# GrblMainboard_-_v3_0.net
KiCad netlist of a schematic drawn in EAGLE
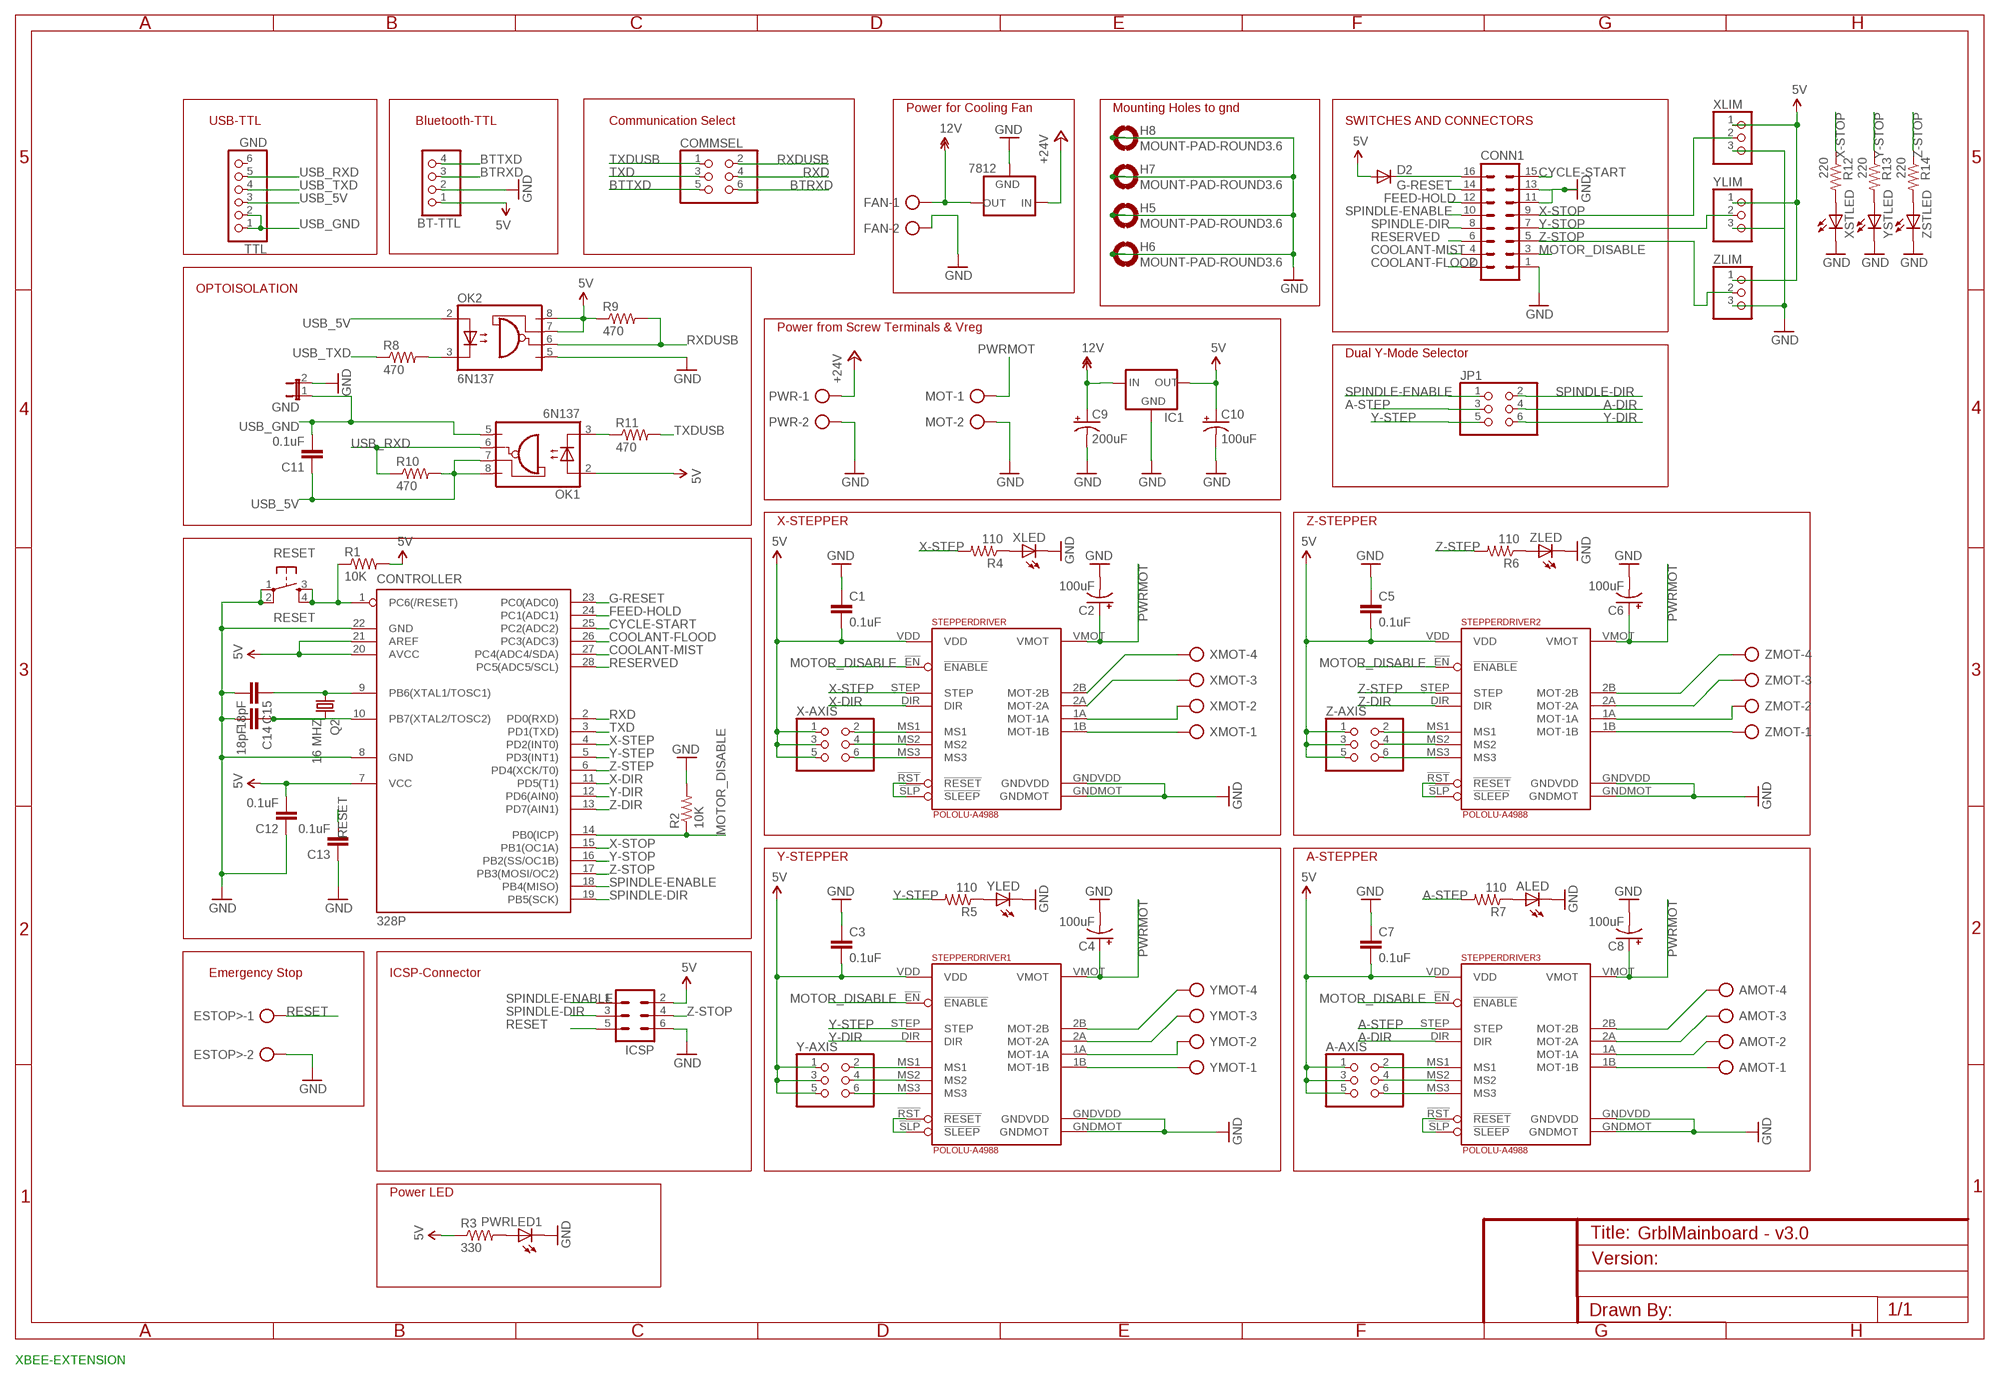
[diagram p0: schematic, sheet 1]

(export (version "E")
  (design (tool "Eeschema 10.0.6"))
  (components
    (comp (ref "328P")
      (value "CONTROLLER")
      (footprint "eagle-import:DIL28-3")
      (libsource (lib "eagle-import") (part "MEGA8-P"))
    )
    (comp (ref "7812")
      (value "V_REG_78XXSINK")
      (footprint "eagle-import:TO220-IGO")
      (libsource (lib "eagle-import") (part "V_REG_78XXSINK"))
    )
    (comp (ref "A-AXIS")
      (value "PINHD-2X3")
      (footprint "eagle-import:2X03")
      (libsource (lib "eagle-import") (part "PINHD-2X3"))
    )
    (comp (ref "ALED")
      (value "LED3MM")
      (footprint "eagle-import:LED3MM")
      (libsource (lib "eagle-import") (part "LED3MM"))
    )
    (comp (ref "AMOT")
      (value "AK500/4")
      (footprint "eagle-import:AK500_4")
      (libsource (lib "eagle-import") (part "AK500/4"))
    )
    (comp (ref "BT-TTL")
      (value "PINHD-1X4")
      (footprint "eagle-import:1X04")
      (libsource (lib "eagle-import") (part "PINHD-1X4"))
    )
    (comp (ref "C1")
      (value "0.1uF")
      (footprint "eagle-import:C025-025X050")
      (libsource (lib "eagle-import") (part "C-EU025-025X050"))
    )
    (comp (ref "C2")
      (value "100uF")
      (footprint "eagle-import:E3,5-8")
      (libsource (lib "eagle-import") (part "CPOL-USE3.5-8"))
    )
    (comp (ref "C3")
      (value "0.1uF")
      (footprint "eagle-import:C025-025X050")
      (libsource (lib "eagle-import") (part "C-EU025-025X050"))
    )
    (comp (ref "C4")
      (value "100uF")
      (footprint "eagle-import:E3,5-8")
      (libsource (lib "eagle-import") (part "CPOL-USE3.5-8"))
    )
    (comp (ref "C5")
      (value "0.1uF")
      (footprint "eagle-import:C025-025X050")
      (libsource (lib "eagle-import") (part "C-EU025-025X050"))
    )
    (comp (ref "C6")
      (value "100uF")
      (footprint "eagle-import:E3,5-8")
      (libsource (lib "eagle-import") (part "CPOL-USE3.5-8"))
    )
    (comp (ref "C7")
      (value "0.1uF")
      (footprint "eagle-import:C025-025X050")
      (libsource (lib "eagle-import") (part "C-EU025-025X050"))
    )
    (comp (ref "C8")
      (value "100uF")
      (footprint "eagle-import:E3,5-8")
      (libsource (lib "eagle-import") (part "CPOL-USE3.5-8"))
    )
    (comp (ref "C9")
      (value "200uF")
      (footprint "eagle-import:E2,5-6")
      (libsource (lib "eagle-import") (part "CPOL-USE2.5-6"))
    )
    (comp (ref "C10")
      (value "100uF")
      (footprint "eagle-import:E2,5-6")
      (libsource (lib "eagle-import") (part "CPOL-USE2.5-6"))
    )
    (comp (ref "C11")
      (value "0.1uF")
      (footprint "eagle-import:C025-025X050")
      (libsource (lib "eagle-import") (part "C-EU025-025X050"))
    )
    (comp (ref "C12")
      (value "0.1uF")
      (footprint "eagle-import:C025-025X050")
      (libsource (lib "eagle-import") (part "C-EU025-025X050"))
    )
    (comp (ref "C13")
      (value "0.1uF")
      (footprint "eagle-import:C025-025X050")
      (libsource (lib "eagle-import") (part "C-EU025-025X050"))
    )
    (comp (ref "C14")
      (value "18pF")
      (footprint "eagle-import:C025-025X050")
      (libsource (lib "eagle-import") (part "C-EU025-025X050"))
    )
    (comp (ref "C15")
      (value "18pF")
      (footprint "eagle-import:C025-025X050")
      (libsource (lib "eagle-import") (part "C-EU025-025X050"))
    )
    (comp (ref "COMMSEL")
      (value "PINHD-2X3")
      (footprint "eagle-import:2X03")
      (libsource (lib "eagle-import") (part "PINHD-2X3"))
    )
    (comp (ref "CONN1")
      (value "ML16")
      (footprint "eagle-import:ML16")
      (libsource (lib "eagle-import") (part "ML16"))
    )
    (comp (ref "D2")
      (value "DIODEPTH")
      (footprint "eagle-import:DIODE-1N4001")
      (libsource (lib "eagle-import") (part "DIODEPTH"))
    )
    (comp (ref "ESTOP>")
      (value "AK500/2")
      (footprint "eagle-import:AK500_2")
      (libsource (lib "eagle-import") (part "AK500/2"))
    )
    (comp (ref "FAN")
      (value "AK500/2")
      (footprint "eagle-import:AK500_2")
      (libsource (lib "eagle-import") (part "AK500/2"))
    )
    (comp (ref "GND")
      (value "JP1E")
      (footprint "eagle-import:JP1")
      (libsource (lib "eagle-import") (part "JP1E"))
    )
    (comp (ref "H5")
      (value "MOUNT-PAD-ROUND3.6")
      (footprint "eagle-import:3,6-PAD")
      (libsource (lib "eagle-import") (part "MOUNT-PAD-ROUND3.6"))
    )
    (comp (ref "H6")
      (value "MOUNT-PAD-ROUND3.6")
      (footprint "eagle-import:3,6-PAD")
      (libsource (lib "eagle-import") (part "MOUNT-PAD-ROUND3.6"))
    )
    (comp (ref "H7")
      (value "MOUNT-PAD-ROUND3.6")
      (footprint "eagle-import:3,6-PAD")
      (libsource (lib "eagle-import") (part "MOUNT-PAD-ROUND3.6"))
    )
    (comp (ref "H8")
      (value "MOUNT-PAD-ROUND3.6")
      (footprint "eagle-import:3,6-PAD")
      (libsource (lib "eagle-import") (part "MOUNT-PAD-ROUND3.6"))
    )
    (comp (ref "IC1")
      (value "V_REG_78XXSINK")
      (footprint "eagle-import:TO220-IGO")
      (libsource (lib "eagle-import") (part "V_REG_78XXSINK"))
    )
    (comp (ref "ICSP")
      (value "ML6")
      (footprint "eagle-import:ML6")
      (libsource (lib "eagle-import") (part "ML6"))
    )
    (comp (ref "JP1")
      (value "PINHD-2X3")
      (footprint "eagle-import:2X03")
      (libsource (lib "eagle-import") (part "PINHD-2X3"))
    )
    (comp (ref "MOT")
      (value "AK500/2")
      (footprint "eagle-import:AK500_2")
      (libsource (lib "eagle-import") (part "AK500/2"))
    )
    (comp (ref "OK1")
      (value "6N137")
      (footprint "eagle-import:DIL08")
      (libsource (lib "eagle-import") (part "6N137"))
    )
    (comp (ref "OK2")
      (value "6N137")
      (footprint "eagle-import:DIL08")
      (libsource (lib "eagle-import") (part "6N137"))
    )
    (comp (ref "PWR")
      (value "AK500/2")
      (footprint "eagle-import:AK500_2")
      (libsource (lib "eagle-import") (part "AK500/2"))
    )
    (comp (ref "PWRLED1")
      (value "LED3MM")
      (footprint "eagle-import:LED3MM")
      (libsource (lib "eagle-import") (part "LED3MM"))
    )
    (comp (ref "Q2")
      (value "16 MHZ")
      (footprint "eagle-import:HC49_S")
      (libsource (lib "eagle-import") (part "CRYSTALHC49S"))
    )
    (comp (ref "R1")
      (value "10K")
      (footprint "eagle-import:AXIAL-0.3")
      (libsource (lib "eagle-import") (part "RESISTORAXIAL-0.3"))
    )
    (comp (ref "R2")
      (value "10K")
      (footprint "eagle-import:AXIAL-0.3")
      (libsource (lib "eagle-import") (part "RESISTORAXIAL-0.3"))
    )
    (comp (ref "R3")
      (value "330")
      (footprint "eagle-import:1_6W-RES")
      (libsource (lib "eagle-import") (part "RESISTORPTH-1/6W"))
    )
    (comp (ref "R4")
      (value "110")
      (footprint "eagle-import:AXIAL-0.3")
      (libsource (lib "eagle-import") (part "RESISTORAXIAL-0.3"))
    )
    (comp (ref "R5")
      (value "110")
      (footprint "eagle-import:AXIAL-0.3")
      (libsource (lib "eagle-import") (part "RESISTORAXIAL-0.3"))
    )
    (comp (ref "R6")
      (value "110")
      (footprint "eagle-import:AXIAL-0.3")
      (libsource (lib "eagle-import") (part "RESISTORAXIAL-0.3"))
    )
    (comp (ref "R7")
      (value "110")
      (footprint "eagle-import:AXIAL-0.3")
      (libsource (lib "eagle-import") (part "RESISTORAXIAL-0.3"))
    )
    (comp (ref "R8")
      (value "470")
      (footprint "eagle-import:AXIAL-0.3")
      (libsource (lib "eagle-import") (part "RESISTORAXIAL-0.3"))
    )
    (comp (ref "R9")
      (value "470")
      (footprint "eagle-import:AXIAL-0.3")
      (libsource (lib "eagle-import") (part "RESISTORAXIAL-0.3"))
    )
    (comp (ref "R10")
      (value "470")
      (footprint "eagle-import:AXIAL-0.3")
      (libsource (lib "eagle-import") (part "RESISTORAXIAL-0.3"))
    )
    (comp (ref "R11")
      (value "470")
      (footprint "eagle-import:AXIAL-0.3")
      (libsource (lib "eagle-import") (part "RESISTORAXIAL-0.3"))
    )
    (comp (ref "R12")
      (value "220")
      (footprint "eagle-import:AXIAL-0.3")
      (libsource (lib "eagle-import") (part "RESISTORAXIAL-0.3"))
    )
    (comp (ref "R13")
      (value "220")
      (footprint "eagle-import:AXIAL-0.3")
      (libsource (lib "eagle-import") (part "RESISTORAXIAL-0.3"))
    )
    (comp (ref "R14")
      (value "220")
      (footprint "eagle-import:AXIAL-0.3")
      (libsource (lib "eagle-import") (part "RESISTORAXIAL-0.3"))
    )
    (comp (ref "RESET")
      (value "RESET")
      (footprint "eagle-import:TACTILE-PTH")
      (libsource (lib "eagle-import") (part "TAC_SWITCHPTH"))
    )
    (comp (ref "STEPPERDRIVER")
      (value "POLOLU-A4988")
      (footprint "eagle-import:POLOLU-ALLEGRO-PTH")
      (libsource (lib "eagle-import") (part "POLOLU-ALLEGRO"))
    )
    (comp (ref "STEPPERDRIVER1")
      (value "POLOLU-A4988")
      (footprint "eagle-import:POLOLU-ALLEGRO-PTH")
      (libsource (lib "eagle-import") (part "POLOLU-ALLEGRO"))
    )
    (comp (ref "STEPPERDRIVER2")
      (value "POLOLU-A4988")
      (footprint "eagle-import:POLOLU-ALLEGRO-PTH")
      (libsource (lib "eagle-import") (part "POLOLU-ALLEGRO"))
    )
    (comp (ref "STEPPERDRIVER3")
      (value "POLOLU-A4988")
      (footprint "eagle-import:POLOLU-ALLEGRO-PTH")
      (libsource (lib "eagle-import") (part "POLOLU-ALLEGRO"))
    )
    (comp (ref "TTL")
      (value "GND")
      (footprint "eagle-import:1X06")
      (libsource (lib "eagle-import") (part "PINHD-1X6"))
    )
    (comp (ref "X-AXIS")
      (value "PINHD-2X3")
      (footprint "eagle-import:2X03")
      (libsource (lib "eagle-import") (part "PINHD-2X3"))
    )
    (comp (ref "XLED")
      (value "LED3MM")
      (footprint "eagle-import:LED3MM")
      (libsource (lib "eagle-import") (part "LED3MM"))
    )
    (comp (ref "XLIM")
      (value "PINHD-1X3")
      (footprint "eagle-import:1X03")
      (libsource (lib "eagle-import") (part "PINHD-1X3"))
    )
    (comp (ref "XMOT")
      (value "AK500/4")
      (footprint "eagle-import:AK500_4")
      (libsource (lib "eagle-import") (part "AK500/4"))
    )
    (comp (ref "XSTLED")
      (value "LED3MM")
      (footprint "eagle-import:LED3MM")
      (libsource (lib "eagle-import") (part "LED3MM"))
    )
    (comp (ref "Y-AXIS")
      (value "PINHD-2X3")
      (footprint "eagle-import:2X03")
      (libsource (lib "eagle-import") (part "PINHD-2X3"))
    )
    (comp (ref "YLED")
      (value "LED3MM")
      (footprint "eagle-import:LED3MM")
      (libsource (lib "eagle-import") (part "LED3MM"))
    )
    (comp (ref "YLIM")
      (value "PINHD-1X3")
      (footprint "eagle-import:1X03")
      (libsource (lib "eagle-import") (part "PINHD-1X3"))
    )
    (comp (ref "YMOT")
      (value "AK500/4")
      (footprint "eagle-import:AK500_4")
      (libsource (lib "eagle-import") (part "AK500/4"))
    )
    (comp (ref "YSTLED")
      (value "LED3MM")
      (footprint "eagle-import:LED3MM")
      (libsource (lib "eagle-import") (part "LED3MM"))
    )
    (comp (ref "Z-AXIS")
      (value "PINHD-2X3")
      (footprint "eagle-import:2X03")
      (libsource (lib "eagle-import") (part "PINHD-2X3"))
    )
    (comp (ref "ZLED")
      (value "LED3MM")
      (footprint "eagle-import:LED3MM")
      (libsource (lib "eagle-import") (part "LED3MM"))
    )
    (comp (ref "ZLIM")
      (value "PINHD-1X3")
      (footprint "eagle-import:1X03")
      (libsource (lib "eagle-import") (part "PINHD-1X3"))
    )
    (comp (ref "ZMOT")
      (value "AK500/4")
      (footprint "eagle-import:AK500_4")
      (libsource (lib "eagle-import") (part "AK500/4"))
    )
    (comp (ref "ZSTLED")
      (value "LED3MM")
      (footprint "eagle-import:LED3MM")
      (libsource (lib "eagle-import") (part "LED3MM"))
    )
  )
  (nets
    (net (code "1") (name "+24V") (class "Default")
      (node (ref "7812") (pin "IN") (pinfunction "IN_IN") (pintype "input"))
      (node (ref "PWR") (pin "1") (pinfunction "KL_1") (pintype "passive"))
    )
    (net (code "2") (name "/A-DIR") (class "Default")
      (node (ref "JP1") (pin "4") (pinfunction "4_4") (pintype "passive"))
      (node (ref "STEPPERDRIVER3") (pin "DIR") (pinfunction "DIR_DIR") (pintype "bidirectional"))
    )
    (net (code "3") (name "/A-STEP") (class "Default")
      (node (ref "JP1") (pin "3") (pinfunction "3_3") (pintype "passive"))
      (node (ref "R7") (pin "P$2") (pinfunction "2_P$2") (pintype "passive"))
      (node (ref "STEPPERDRIVER3") (pin "STEP") (pinfunction "STEP_STEP") (pintype "bidirectional"))
    )
    (net (code "4") (name "/BTRXD") (class "Default")
      (node (ref "BT-TTL") (pin "3") (pinfunction "3_3") (pintype "passive"))
      (node (ref "COMMSEL") (pin "6") (pinfunction "6_6") (pintype "passive"))
    )
    (net (code "5") (name "/BTTXD") (class "Default")
      (node (ref "BT-TTL") (pin "4") (pinfunction "4_4") (pintype "passive"))
      (node (ref "COMMSEL") (pin "5") (pinfunction "5_5") (pintype "passive"))
    )
    (net (code "6") (name "/COOLANT-FLOOD") (class "Default")
      (node (ref "328P") (pin "26") (pinfunction "PC3(ADC3)_26") (pintype "bidirectional"))
      (node (ref "CONN1") (pin "2") (pinfunction "2_2") (pintype "passive"))
    )
    (net (code "7") (name "/COOLANT-MIST") (class "Default")
      (node (ref "328P") (pin "27") (pinfunction "PC4(ADC4/SDA)_27") (pintype "bidirectional"))
      (node (ref "CONN1") (pin "4") (pinfunction "4_4") (pintype "passive"))
    )
    (net (code "8") (name "/CYCLE-START") (class "Default")
      (node (ref "328P") (pin "25") (pinfunction "PC2(ADC2)_25") (pintype "bidirectional"))
      (node (ref "CONN1") (pin "15") (pinfunction "15_15") (pintype "passive"))
    )
    (net (code "9") (name "/FEED-HOLD") (class "Default")
      (node (ref "328P") (pin "24") (pinfunction "PC1(ADC1)_24") (pintype "bidirectional"))
      (node (ref "CONN1") (pin "12") (pinfunction "12_12") (pintype "passive"))
    )
    (net (code "10") (name "/G-RESET") (class "Default")
      (node (ref "328P") (pin "23") (pinfunction "PC0(ADC0)_23") (pintype "bidirectional"))
      (node (ref "CONN1") (pin "14") (pinfunction "14_14") (pintype "passive"))
    )
    (net (code "11") (name "/MOTOR_DISABLE") (class "Default")
      (node (ref "328P") (pin "14") (pinfunction "PB0(ICP)_14") (pintype "bidirectional"))
      (node (ref "CONN1") (pin "3") (pinfunction "3_3") (pintype "passive"))
      (node (ref "R2") (pin "P$1") (pinfunction "1_P$1") (pintype "passive"))
      (node (ref "STEPPERDRIVER") (pin "!EN") (pinfunction "~{ENABLE}_!EN") (pintype "input"))
      (node (ref "STEPPERDRIVER1") (pin "!EN") (pinfunction "~{ENABLE}_!EN") (pintype "input"))
      (node (ref "STEPPERDRIVER2") (pin "!EN") (pinfunction "~{ENABLE}_!EN") (pintype "input"))
      (node (ref "STEPPERDRIVER3") (pin "!EN") (pinfunction "~{ENABLE}_!EN") (pintype "input"))
    )
    (net (code "12") (name "/PWRMOT") (class "Default")
      (node (ref "C2") (pin "+") (pinfunction "+_+") (pintype "passive"))
      (node (ref "C4") (pin "+") (pinfunction "+_+") (pintype "passive"))
      (node (ref "C6") (pin "+") (pinfunction "+_+") (pintype "passive"))
      (node (ref "C8") (pin "+") (pinfunction "+_+") (pintype "passive"))
      (node (ref "MOT") (pin "1") (pinfunction "KL_1") (pintype "passive"))
      (node (ref "STEPPERDRIVER") (pin "VMOT") (pinfunction "VMOT_VMOT") (pintype "power_in"))
      (node (ref "STEPPERDRIVER1") (pin "VMOT") (pinfunction "VMOT_VMOT") (pintype "power_in"))
      (node (ref "STEPPERDRIVER2") (pin "VMOT") (pinfunction "VMOT_VMOT") (pintype "power_in"))
      (node (ref "STEPPERDRIVER3") (pin "VMOT") (pinfunction "VMOT_VMOT") (pintype "power_in"))
    )
    (net (code "13") (name "/RESERVED") (class "Default")
      (node (ref "328P") (pin "28") (pinfunction "PC5(ADC5/SCL)_28") (pintype "bidirectional"))
      (node (ref "CONN1") (pin "6") (pinfunction "6_6") (pintype "passive"))
    )
    (net (code "14") (name "/RESET") (class "Default")
      (node (ref "328P") (pin "1") (pinfunction "PC6(/RESET)_1") (pintype "bidirectional"))
      (node (ref "C13") (pin "2") (pinfunction "2_2") (pintype "passive"))
      (node (ref "ESTOP>") (pin "1") (pinfunction "KL_1") (pintype "passive"))
      (node (ref "ICSP") (pin "5") (pinfunction "5_5") (pintype "passive"))
      (node (ref "R1") (pin "P$1") (pinfunction "1_P$1") (pintype "passive"))
      (node (ref "RESET") (pin "3") (pinfunction "3_3") (pintype "passive"))
      (node (ref "RESET") (pin "4") (pinfunction "4_4") (pintype "passive"))
    )
    (net (code "15") (name "/RXD") (class "Default")
      (node (ref "328P") (pin "2") (pinfunction "PD0(RXD)_2") (pintype "bidirectional"))
      (node (ref "COMMSEL") (pin "4") (pinfunction "4_4") (pintype "passive"))
    )
    (net (code "16") (name "/RXDUSB") (class "Default")
      (node (ref "COMMSEL") (pin "2") (pinfunction "2_2") (pintype "passive"))
      (node (ref "OK2") (pin "6") (pinfunction "VO_6") (pintype "passive"))
      (node (ref "R9") (pin "P$2") (pinfunction "2_P$2") (pintype "passive"))
    )
    (net (code "17") (name "/SPINDLE-DIR") (class "Default")
      (node (ref "328P") (pin "19") (pinfunction "PB5(SCK)_19") (pintype "bidirectional"))
      (node (ref "CONN1") (pin "8") (pinfunction "8_8") (pintype "passive"))
      (node (ref "ICSP") (pin "3") (pinfunction "3_3") (pintype "passive"))
      (node (ref "JP1") (pin "2") (pinfunction "2_2") (pintype "passive"))
    )
    (net (code "18") (name "/SPINDLE-ENABLE") (class "Default")
      (node (ref "328P") (pin "18") (pinfunction "PB4(MISO)_18") (pintype "bidirectional"))
      (node (ref "CONN1") (pin "10") (pinfunction "10_10") (pintype "passive"))
      (node (ref "ICSP") (pin "1") (pinfunction "1_1") (pintype "passive"))
      (node (ref "JP1") (pin "1") (pinfunction "1_1") (pintype "passive"))
    )
    (net (code "19") (name "/TXD") (class "Default")
      (node (ref "328P") (pin "3") (pinfunction "PD1(TXD)_3") (pintype "bidirectional"))
      (node (ref "COMMSEL") (pin "3") (pinfunction "3_3") (pintype "passive"))
    )
    (net (code "20") (name "/TXDUSB") (class "Default")
      (node (ref "COMMSEL") (pin "1") (pinfunction "1_1") (pintype "passive"))
      (node (ref "R11") (pin "P$2") (pinfunction "2_P$2") (pintype "passive"))
    )
    (net (code "21") (name "/USB_5V") (class "Default")
      (node (ref "C11") (pin "1") (pinfunction "1_1") (pintype "passive"))
      (node (ref "OK1") (pin "7") (pinfunction "VE_7") (pintype "passive"))
      (node (ref "OK1") (pin "8") (pinfunction "VCC_8") (pintype "passive"))
      (node (ref "OK2") (pin "2") (pinfunction "A_2") (pintype "passive"))
      (node (ref "R10") (pin "P$2") (pinfunction "2_P$2") (pintype "passive"))
      (node (ref "TTL") (pin "3") (pinfunction "3_3") (pintype "passive"))
    )
    (net (code "22") (name "/USB_GND") (class "Default")
      (node (ref "C11") (pin "2") (pinfunction "2_2") (pintype "passive"))
      (node (ref "GND") (pin "1") (pinfunction "1_1") (pintype "passive"))
      (node (ref "OK1") (pin "5") (pinfunction "GND_5") (pintype "passive"))
      (node (ref "TTL") (pin "1") (pinfunction "1_1") (pintype "passive"))
      (node (ref "TTL") (pin "2") (pinfunction "2_2") (pintype "passive"))
    )
    (net (code "23") (name "/USB_RXD") (class "Default")
      (node (ref "OK1") (pin "6") (pinfunction "VO_6") (pintype "passive"))
      (node (ref "R10") (pin "P$1") (pinfunction "1_P$1") (pintype "passive"))
      (node (ref "TTL") (pin "5") (pinfunction "5_5") (pintype "passive"))
    )
    (net (code "24") (name "/USB_TXD") (class "Default")
      (node (ref "R8") (pin "P$1") (pinfunction "1_P$1") (pintype "passive"))
      (node (ref "TTL") (pin "4") (pinfunction "4_4") (pintype "passive"))
    )
    (net (code "25") (name "/X-DIR") (class "Default")
      (node (ref "328P") (pin "11") (pinfunction "PD5(T1)_11") (pintype "bidirectional"))
      (node (ref "STEPPERDRIVER") (pin "DIR") (pinfunction "DIR_DIR") (pintype "bidirectional"))
    )
    (net (code "26") (name "/X-STEP") (class "Default")
      (node (ref "328P") (pin "4") (pinfunction "PD2(INT0)_4") (pintype "bidirectional"))
      (node (ref "R4") (pin "P$2") (pinfunction "2_P$2") (pintype "passive"))
      (node (ref "STEPPERDRIVER") (pin "STEP") (pinfunction "STEP_STEP") (pintype "bidirectional"))
    )
    (net (code "27") (name "/X-STOP") (class "Default")
      (node (ref "328P") (pin "15") (pinfunction "PB1(OC1A)_15") (pintype "bidirectional"))
      (node (ref "CONN1") (pin "9") (pinfunction "9_9") (pintype "passive"))
      (node (ref "R12") (pin "P$1") (pinfunction "1_P$1") (pintype "passive"))
      (node (ref "XLIM") (pin "2") (pinfunction "2_2") (pintype "passive"))
    )
    (net (code "28") (name "/Y-DIR") (class "Default")
      (node (ref "328P") (pin "12") (pinfunction "PD6(AIN0)_12") (pintype "bidirectional"))
      (node (ref "JP1") (pin "6") (pinfunction "6_6") (pintype "passive"))
      (node (ref "STEPPERDRIVER1") (pin "DIR") (pinfunction "DIR_DIR") (pintype "bidirectional"))
    )
    (net (code "29") (name "/Y-STEP") (class "Default")
      (node (ref "328P") (pin "5") (pinfunction "PD3(INT1)_5") (pintype "bidirectional"))
      (node (ref "JP1") (pin "5") (pinfunction "5_5") (pintype "passive"))
      (node (ref "R5") (pin "P$2") (pinfunction "2_P$2") (pintype "passive"))
      (node (ref "STEPPERDRIVER1") (pin "STEP") (pinfunction "STEP_STEP") (pintype "bidirectional"))
    )
    (net (code "30") (name "/Y-STOP") (class "Default")
      (node (ref "328P") (pin "16") (pinfunction "PB2(SS/OC1B)_16") (pintype "bidirectional"))
      (node (ref "CONN1") (pin "7") (pinfunction "7_7") (pintype "passive"))
      (node (ref "R13") (pin "P$1") (pinfunction "1_P$1") (pintype "passive"))
      (node (ref "YLIM") (pin "2") (pinfunction "2_2") (pintype "passive"))
    )
    (net (code "31") (name "/Z-DIR") (class "Default")
      (node (ref "328P") (pin "13") (pinfunction "PD7(AIN1)_13") (pintype "bidirectional"))
      (node (ref "STEPPERDRIVER2") (pin "DIR") (pinfunction "DIR_DIR") (pintype "bidirectional"))
    )
    (net (code "32") (name "/Z-STEP") (class "Default")
      (node (ref "328P") (pin "6") (pinfunction "PD4(XCK/T0)_6") (pintype "bidirectional"))
      (node (ref "R6") (pin "P$2") (pinfunction "2_P$2") (pintype "passive"))
      (node (ref "STEPPERDRIVER2") (pin "STEP") (pinfunction "STEP_STEP") (pintype "bidirectional"))
    )
    (net (code "33") (name "/Z-STOP") (class "Default")
      (node (ref "328P") (pin "17") (pinfunction "PB3(MOSI/OC2)_17") (pintype "bidirectional"))
      (node (ref "CONN1") (pin "5") (pinfunction "5_5") (pintype "passive"))
      (node (ref "ICSP") (pin "4") (pinfunction "4_4") (pintype "passive"))
      (node (ref "R14") (pin "P$1") (pinfunction "1_P$1") (pintype "passive"))
      (node (ref "ZLIM") (pin "2") (pinfunction "2_2") (pintype "passive"))
    )
    (net (code "34") (name "5V") (class "Default")
      (node (ref "328P") (pin "20") (pinfunction "AVCC_20") (pintype "power_in"))
      (node (ref "328P") (pin "21") (pinfunction "AREF_21") (pintype "passive"))
      (node (ref "328P") (pin "7") (pinfunction "VCC_7") (pintype "power_in"))
      (node (ref "A-AXIS") (pin "1") (pinfunction "1_1") (pintype "passive"))
      (node (ref "A-AXIS") (pin "3") (pinfunction "3_3") (pintype "passive"))
      (node (ref "A-AXIS") (pin "5") (pinfunction "5_5") (pintype "passive"))
      (node (ref "BT-TTL") (pin "1") (pinfunction "1_1") (pintype "passive"))
      (node (ref "C1") (pin "2") (pinfunction "2_2") (pintype "passive"))
      (node (ref "C10") (pin "+") (pinfunction "+_+") (pintype "passive"))
      (node (ref "C12") (pin "2") (pinfunction "2_2") (pintype "passive"))
      (node (ref "C3") (pin "2") (pinfunction "2_2") (pintype "passive"))
      (node (ref "C5") (pin "2") (pinfunction "2_2") (pintype "passive"))
      (node (ref "C7") (pin "2") (pinfunction "2_2") (pintype "passive"))
      (node (ref "D2") (pin "A") (pinfunction "A_A") (pintype "passive"))
      (node (ref "IC1") (pin "OUT") (pinfunction "OUT_OUT") (pintype "output"))
      (node (ref "ICSP") (pin "2") (pinfunction "2_2") (pintype "passive"))
      (node (ref "OK1") (pin "2") (pinfunction "A_2") (pintype "passive"))
      (node (ref "OK2") (pin "7") (pinfunction "VE_7") (pintype "passive"))
      (node (ref "OK2") (pin "8") (pinfunction "VCC_8") (pintype "passive"))
      (node (ref "R1") (pin "P$2") (pinfunction "2_P$2") (pintype "passive"))
      (node (ref "R3") (pin "1") (pinfunction "1_1") (pintype "passive"))
      (node (ref "R9") (pin "P$1") (pinfunction "1_P$1") (pintype "passive"))
      (node (ref "STEPPERDRIVER") (pin "VDD") (pinfunction "VDD_VDD") (pintype "power_in"))
      (node (ref "STEPPERDRIVER1") (pin "VDD") (pinfunction "VDD_VDD") (pintype "power_in"))
      (node (ref "STEPPERDRIVER2") (pin "VDD") (pinfunction "VDD_VDD") (pintype "power_in"))
      (node (ref "STEPPERDRIVER3") (pin "VDD") (pinfunction "VDD_VDD") (pintype "power_in"))
      (node (ref "X-AXIS") (pin "1") (pinfunction "1_1") (pintype "passive"))
      (node (ref "X-AXIS") (pin "3") (pinfunction "3_3") (pintype "passive"))
      (node (ref "X-AXIS") (pin "5") (pinfunction "5_5") (pintype "passive"))
      (node (ref "XLIM") (pin "1") (pinfunction "1_1") (pintype "passive"))
      (node (ref "Y-AXIS") (pin "1") (pinfunction "1_1") (pintype "passive"))
      (node (ref "Y-AXIS") (pin "3") (pinfunction "3_3") (pintype "passive"))
      (node (ref "Y-AXIS") (pin "5") (pinfunction "5_5") (pintype "passive"))
      (node (ref "YLIM") (pin "1") (pinfunction "1_1") (pintype "passive"))
      (node (ref "Z-AXIS") (pin "1") (pinfunction "1_1") (pintype "passive"))
      (node (ref "Z-AXIS") (pin "3") (pinfunction "3_3") (pintype "passive"))
      (node (ref "Z-AXIS") (pin "5") (pinfunction "5_5") (pintype "passive"))
      (node (ref "ZLIM") (pin "1") (pinfunction "1_1") (pintype "passive"))
    )
    (net (code "35") (name "12V") (class "Default")
      (node (ref "7812") (pin "OUT") (pinfunction "OUT_OUT") (pintype "output"))
      (node (ref "C9") (pin "+") (pinfunction "+_+") (pintype "passive"))
      (node (ref "FAN") (pin "1") (pinfunction "KL_1") (pintype "passive"))
      (node (ref "IC1") (pin "IN") (pinfunction "IN_IN") (pintype "input"))
    )
    (net (code "36") (name "GND") (class "Default")
      (node (ref "328P") (pin "22") (pinfunction "GND_22") (pintype "power_in"))
      (node (ref "328P") (pin "8") (pinfunction "GND_8") (pintype "power_in"))
      (node (ref "7812") (pin "GND") (pinfunction "GND_GND") (pintype "input"))
      (node (ref "ALED") (pin "K") (pinfunction "C_K") (pintype "passive"))
      (node (ref "BT-TTL") (pin "2") (pinfunction "2_2") (pintype "passive"))
      (node (ref "C1") (pin "1") (pinfunction "1_1") (pintype "passive"))
      (node (ref "C10") (pin "-") (pinfunction "-_-") (pintype "passive"))
      (node (ref "C12") (pin "1") (pinfunction "1_1") (pintype "passive"))
      (node (ref "C13") (pin "1") (pinfunction "1_1") (pintype "passive"))
      (node (ref "C14") (pin "2") (pinfunction "2_2") (pintype "passive"))
      (node (ref "C15") (pin "2") (pinfunction "2_2") (pintype "passive"))
      (node (ref "C2") (pin "-") (pinfunction "-_-") (pintype "passive"))
      (node (ref "C3") (pin "1") (pinfunction "1_1") (pintype "passive"))
      (node (ref "C4") (pin "-") (pinfunction "-_-") (pintype "passive"))
      (node (ref "C5") (pin "1") (pinfunction "1_1") (pintype "passive"))
      (node (ref "C6") (pin "-") (pinfunction "-_-") (pintype "passive"))
      (node (ref "C7") (pin "1") (pinfunction "1_1") (pintype "passive"))
      (node (ref "C8") (pin "-") (pinfunction "-_-") (pintype "passive"))
      (node (ref "C9") (pin "-") (pinfunction "-_-") (pintype "passive"))
      (node (ref "CONN1") (pin "1") (pinfunction "1_1") (pintype "passive"))
      (node (ref "CONN1") (pin "11") (pinfunction "11_11") (pintype "passive"))
      (node (ref "CONN1") (pin "13") (pinfunction "13_13") (pintype "passive"))
      (node (ref "ESTOP>") (pin "2") (pinfunction "KL_2") (pintype "passive"))
      (node (ref "FAN") (pin "2") (pinfunction "KL_2") (pintype "passive"))
      (node (ref "GND") (pin "2") (pinfunction "2_2") (pintype "passive"))
      (node (ref "H5") (pin "B3,6") (pinfunction "MOUNT_B3,6") (pintype "passive"))
      (node (ref "H6") (pin "B3,6") (pinfunction "MOUNT_B3,6") (pintype "passive"))
      (node (ref "H7") (pin "B3,6") (pinfunction "MOUNT_B3,6") (pintype "passive"))
      (node (ref "H8") (pin "B3,6") (pinfunction "MOUNT_B3,6") (pintype "passive"))
      (node (ref "IC1") (pin "GND") (pinfunction "GND_GND") (pintype "input"))
      (node (ref "ICSP") (pin "6") (pinfunction "6_6") (pintype "passive"))
      (node (ref "MOT") (pin "2") (pinfunction "KL_2") (pintype "passive"))
      (node (ref "OK2") (pin "5") (pinfunction "GND_5") (pintype "passive"))
      (node (ref "PWR") (pin "2") (pinfunction "KL_2") (pintype "passive"))
      (node (ref "PWRLED1") (pin "K") (pinfunction "C_K") (pintype "passive"))
      (node (ref "R2") (pin "P$2") (pinfunction "2_P$2") (pintype "passive"))
      (node (ref "RESET") (pin "1") (pinfunction "1_1") (pintype "passive"))
      (node (ref "RESET") (pin "2") (pinfunction "2_2") (pintype "passive"))
      (node (ref "STEPPERDRIVER") (pin "GNDMOT") (pinfunction "GNDMOT_GNDMOT") (pintype "power_in"))
      (node (ref "STEPPERDRIVER") (pin "GNDVDD") (pinfunction "GNDVDD_GNDVDD") (pintype "power_in"))
      (node (ref "STEPPERDRIVER1") (pin "GNDMOT") (pinfunction "GNDMOT_GNDMOT") (pintype "power_in"))
      (node (ref "STEPPERDRIVER1") (pin "GNDVDD") (pinfunction "GNDVDD_GNDVDD") (pintype "power_in"))
      (node (ref "STEPPERDRIVER2") (pin "GNDMOT") (pinfunction "GNDMOT_GNDMOT") (pintype "power_in"))
      (node (ref "STEPPERDRIVER2") (pin "GNDVDD") (pinfunction "GNDVDD_GNDVDD") (pintype "power_in"))
      (node (ref "STEPPERDRIVER3") (pin "GNDMOT") (pinfunction "GNDMOT_GNDMOT") (pintype "power_in"))
      (node (ref "STEPPERDRIVER3") (pin "GNDVDD") (pinfunction "GNDVDD_GNDVDD") (pintype "power_in"))
      (node (ref "XLED") (pin "K") (pinfunction "C_K") (pintype "passive"))
      (node (ref "XLIM") (pin "3") (pinfunction "3_3") (pintype "passive"))
      (node (ref "XSTLED") (pin "K") (pinfunction "C_K") (pintype "passive"))
      (node (ref "YLED") (pin "K") (pinfunction "C_K") (pintype "passive"))
      (node (ref "YLIM") (pin "3") (pinfunction "3_3") (pintype "passive"))
      (node (ref "YSTLED") (pin "K") (pinfunction "C_K") (pintype "passive"))
      (node (ref "ZLED") (pin "K") (pinfunction "C_K") (pintype "passive"))
      (node (ref "ZLIM") (pin "3") (pinfunction "3_3") (pintype "passive"))
      (node (ref "ZSTLED") (pin "K") (pinfunction "C_K") (pintype "passive"))
    )
    (net (code "37") (name "Net-(328P-PB6(XTAL1{slash}TOSC1))") (class "Default")
      (node (ref "328P") (pin "9") (pinfunction "PB6(XTAL1/TOSC1)_9") (pintype "bidirectional"))
      (node (ref "C15") (pin "1") (pinfunction "1_1") (pintype "passive"))
      (node (ref "Q2") (pin "1") (pinfunction "1_1") (pintype "passive"))
    )
    (net (code "38") (name "Net-(328P-PB7(XTAL2{slash}TOSC2))") (class "Default")
      (node (ref "328P") (pin "10") (pinfunction "PB7(XTAL2/TOSC2)_10") (pintype "bidirectional"))
      (node (ref "C14") (pin "1") (pinfunction "1_1") (pintype "passive"))
      (node (ref "Q2") (pin "2") (pinfunction "2_2") (pintype "passive"))
    )
    (net (code "39") (name "Net-(A-AXIS-Pad2)") (class "Default")
      (node (ref "A-AXIS") (pin "2") (pinfunction "2_2") (pintype "passive"))
      (node (ref "STEPPERDRIVER3") (pin "MS1") (pinfunction "MS1_MS1") (pintype "input"))
    )
    (net (code "40") (name "Net-(A-AXIS-Pad4)") (class "Default")
      (node (ref "A-AXIS") (pin "4") (pinfunction "4_4") (pintype "passive"))
      (node (ref "STEPPERDRIVER3") (pin "MS2") (pinfunction "MS2_MS2") (pintype "input"))
    )
    (net (code "41") (name "Net-(A-AXIS-Pad6)") (class "Default")
      (node (ref "A-AXIS") (pin "6") (pinfunction "6_6") (pintype "passive"))
      (node (ref "STEPPERDRIVER3") (pin "MS3") (pinfunction "MS3_MS3") (pintype "input"))
    )
    (net (code "42") (name "Net-(AMOTA-KL)") (class "Default")
      (node (ref "AMOT") (pin "1") (pinfunction "KL_1") (pintype "passive"))
      (node (ref "STEPPERDRIVER3") (pin "1B") (pinfunction "MOT-1B_1B") (pintype "power_in"))
    )
    (net (code "43") (name "Net-(AMOTB-KL)") (class "Default")
      (node (ref "AMOT") (pin "2") (pinfunction "KL_2") (pintype "passive"))
      (node (ref "STEPPERDRIVER3") (pin "1A") (pinfunction "MOT-1A_1A") (pintype "power_in"))
    )
    (net (code "44") (name "Net-(AMOTC-KL)") (class "Default")
      (node (ref "AMOT") (pin "3") (pinfunction "KL_3") (pintype "passive"))
      (node (ref "STEPPERDRIVER3") (pin "2A") (pinfunction "MOT-2A_2A") (pintype "power_in"))
    )
    (net (code "45") (name "Net-(AMOTD-KL)") (class "Default")
      (node (ref "AMOT") (pin "4") (pinfunction "KL_4") (pintype "passive"))
      (node (ref "STEPPERDRIVER3") (pin "2B") (pinfunction "MOT-2B_2B") (pintype "power_in"))
    )
    (net (code "46") (name "Net-(CONN1-Pad16)") (class "Default")
      (node (ref "CONN1") (pin "16") (pinfunction "16_16") (pintype "passive"))
      (node (ref "D2") (pin "C") (pinfunction "C_C") (pintype "passive"))
    )
    (net (code "47") (name "Net-(OK1-C)") (class "Default")
      (node (ref "OK1") (pin "3") (pinfunction "C_3") (pintype "passive"))
      (node (ref "R11") (pin "P$1") (pinfunction "1_P$1") (pintype "passive"))
    )
    (net (code "48") (name "Net-(OK2-C)") (class "Default")
      (node (ref "OK2") (pin "3") (pinfunction "C_3") (pintype "passive"))
      (node (ref "R8") (pin "P$2") (pinfunction "2_P$2") (pintype "passive"))
    )
    (net (code "49") (name "Net-(PWRLED1-PadA)") (class "Default")
      (node (ref "PWRLED1") (pin "A") (pinfunction "A_A") (pintype "passive"))
      (node (ref "R3") (pin "2") (pinfunction "2_2") (pintype "passive"))
    )
    (net (code "50") (name "Net-(R4-1)") (class "Default")
      (node (ref "R4") (pin "P$1") (pinfunction "1_P$1") (pintype "passive"))
      (node (ref "XLED") (pin "A") (pinfunction "A_A") (pintype "passive"))
    )
    (net (code "51") (name "Net-(R5-1)") (class "Default")
      (node (ref "R5") (pin "P$1") (pinfunction "1_P$1") (pintype "passive"))
      (node (ref "YLED") (pin "A") (pinfunction "A_A") (pintype "passive"))
    )
    (net (code "52") (name "Net-(R6-1)") (class "Default")
      (node (ref "R6") (pin "P$1") (pinfunction "1_P$1") (pintype "passive"))
      (node (ref "ZLED") (pin "A") (pinfunction "A_A") (pintype "passive"))
    )
    (net (code "53") (name "Net-(R7-1)") (class "Default")
      (node (ref "ALED") (pin "A") (pinfunction "A_A") (pintype "passive"))
      (node (ref "R7") (pin "P$1") (pinfunction "1_P$1") (pintype "passive"))
    )
    (net (code "54") (name "Net-(R12-2)") (class "Default")
      (node (ref "R12") (pin "P$2") (pinfunction "2_P$2") (pintype "passive"))
      (node (ref "XSTLED") (pin "A") (pinfunction "A_A") (pintype "passive"))
    )
    (net (code "55") (name "Net-(R13-2)") (class "Default")
      (node (ref "R13") (pin "P$2") (pinfunction "2_P$2") (pintype "passive"))
      (node (ref "YSTLED") (pin "A") (pinfunction "A_A") (pintype "passive"))
    )
    (net (code "56") (name "Net-(R14-2)") (class "Default")
      (node (ref "R14") (pin "P$2") (pinfunction "2_P$2") (pintype "passive"))
      (node (ref "ZSTLED") (pin "A") (pinfunction "A_A") (pintype "passive"))
    )
    (net (code "57") (name "Net-(STEPPERDRIVER-MOT-1A)") (class "Default")
      (node (ref "STEPPERDRIVER") (pin "1A") (pinfunction "MOT-1A_1A") (pintype "power_in"))
      (node (ref "XMOT") (pin "2") (pinfunction "KL_2") (pintype "passive"))
    )
    (net (code "58") (name "Net-(STEPPERDRIVER-MOT-1B)") (class "Default")
      (node (ref "STEPPERDRIVER") (pin "1B") (pinfunction "MOT-1B_1B") (pintype "power_in"))
      (node (ref "XMOT") (pin "1") (pinfunction "KL_1") (pintype "passive"))
    )
    (net (code "59") (name "Net-(STEPPERDRIVER-MOT-2A)") (class "Default")
      (node (ref "STEPPERDRIVER") (pin "2A") (pinfunction "MOT-2A_2A") (pintype "power_in"))
      (node (ref "XMOT") (pin "3") (pinfunction "KL_3") (pintype "passive"))
    )
    (net (code "60") (name "Net-(STEPPERDRIVER-MOT-2B)") (class "Default")
      (node (ref "STEPPERDRIVER") (pin "2B") (pinfunction "MOT-2B_2B") (pintype "power_in"))
      (node (ref "XMOT") (pin "4") (pinfunction "KL_4") (pintype "passive"))
    )
    (net (code "61") (name "Net-(STEPPERDRIVER-PadMS1)") (class "Default")
      (node (ref "STEPPERDRIVER") (pin "MS1") (pinfunction "MS1_MS1") (pintype "input"))
      (node (ref "X-AXIS") (pin "2") (pinfunction "2_2") (pintype "passive"))
    )
    (net (code "62") (name "Net-(STEPPERDRIVER-PadMS2)") (class "Default")
      (node (ref "STEPPERDRIVER") (pin "MS2") (pinfunction "MS2_MS2") (pintype "input"))
      (node (ref "X-AXIS") (pin "4") (pinfunction "4_4") (pintype "passive"))
    )
    (net (code "63") (name "Net-(STEPPERDRIVER-PadMS3)") (class "Default")
      (node (ref "STEPPERDRIVER") (pin "MS3") (pinfunction "MS3_MS3") (pintype "input"))
      (node (ref "X-AXIS") (pin "6") (pinfunction "6_6") (pintype "passive"))
    )
    (net (code "64") (name "Net-(STEPPERDRIVER-~{RESET})") (class "Default")
      (node (ref "STEPPERDRIVER") (pin "!RST") (pinfunction "~{RESET}_!RST") (pintype "input"))
      (node (ref "STEPPERDRIVER") (pin "!SLP") (pinfunction "~{SLEEP}_!SLP") (pintype "input"))
    )
    (net (code "65") (name "Net-(STEPPERDRIVER1-MOT-1A)") (class "Default")
      (node (ref "STEPPERDRIVER1") (pin "1A") (pinfunction "MOT-1A_1A") (pintype "power_in"))
      (node (ref "YMOT") (pin "2") (pinfunction "KL_2") (pintype "passive"))
    )
    (net (code "66") (name "Net-(STEPPERDRIVER1-MOT-1B)") (class "Default")
      (node (ref "STEPPERDRIVER1") (pin "1B") (pinfunction "MOT-1B_1B") (pintype "power_in"))
      (node (ref "YMOT") (pin "1") (pinfunction "KL_1") (pintype "passive"))
    )
    (net (code "67") (name "Net-(STEPPERDRIVER1-MOT-2A)") (class "Default")
      (node (ref "STEPPERDRIVER1") (pin "2A") (pinfunction "MOT-2A_2A") (pintype "power_in"))
      (node (ref "YMOT") (pin "3") (pinfunction "KL_3") (pintype "passive"))
    )
    (net (code "68") (name "Net-(STEPPERDRIVER1-MOT-2B)") (class "Default")
      (node (ref "STEPPERDRIVER1") (pin "2B") (pinfunction "MOT-2B_2B") (pintype "power_in"))
      (node (ref "YMOT") (pin "4") (pinfunction "KL_4") (pintype "passive"))
    )
    (net (code "69") (name "Net-(STEPPERDRIVER1-PadMS1)") (class "Default")
      (node (ref "STEPPERDRIVER1") (pin "MS1") (pinfunction "MS1_MS1") (pintype "input"))
      (node (ref "Y-AXIS") (pin "2") (pinfunction "2_2") (pintype "passive"))
    )
    (net (code "70") (name "Net-(STEPPERDRIVER1-PadMS2)") (class "Default")
      (node (ref "STEPPERDRIVER1") (pin "MS2") (pinfunction "MS2_MS2") (pintype "input"))
      (node (ref "Y-AXIS") (pin "4") (pinfunction "4_4") (pintype "passive"))
    )
    (net (code "71") (name "Net-(STEPPERDRIVER1-PadMS3)") (class "Default")
      (node (ref "STEPPERDRIVER1") (pin "MS3") (pinfunction "MS3_MS3") (pintype "input"))
      (node (ref "Y-AXIS") (pin "6") (pinfunction "6_6") (pintype "passive"))
    )
    (net (code "72") (name "Net-(STEPPERDRIVER1-~{RESET})") (class "Default")
      (node (ref "STEPPERDRIVER1") (pin "!RST") (pinfunction "~{RESET}_!RST") (pintype "input"))
      (node (ref "STEPPERDRIVER1") (pin "!SLP") (pinfunction "~{SLEEP}_!SLP") (pintype "input"))
    )
    (net (code "73") (name "Net-(STEPPERDRIVER2-MOT-1A)") (class "Default")
      (node (ref "STEPPERDRIVER2") (pin "1A") (pinfunction "MOT-1A_1A") (pintype "power_in"))
      (node (ref "ZMOT") (pin "2") (pinfunction "KL_2") (pintype "passive"))
    )
    (net (code "74") (name "Net-(STEPPERDRIVER2-MOT-1B)") (class "Default")
      (node (ref "STEPPERDRIVER2") (pin "1B") (pinfunction "MOT-1B_1B") (pintype "power_in"))
      (node (ref "ZMOT") (pin "1") (pinfunction "KL_1") (pintype "passive"))
    )
    (net (code "75") (name "Net-(STEPPERDRIVER2-MOT-2A)") (class "Default")
      (node (ref "STEPPERDRIVER2") (pin "2A") (pinfunction "MOT-2A_2A") (pintype "power_in"))
      (node (ref "ZMOT") (pin "3") (pinfunction "KL_3") (pintype "passive"))
    )
    (net (code "76") (name "Net-(STEPPERDRIVER2-MOT-2B)") (class "Default")
      (node (ref "STEPPERDRIVER2") (pin "2B") (pinfunction "MOT-2B_2B") (pintype "power_in"))
      (node (ref "ZMOT") (pin "4") (pinfunction "KL_4") (pintype "passive"))
    )
    (net (code "77") (name "Net-(STEPPERDRIVER2-PadMS1)") (class "Default")
      (node (ref "STEPPERDRIVER2") (pin "MS1") (pinfunction "MS1_MS1") (pintype "input"))
      (node (ref "Z-AXIS") (pin "2") (pinfunction "2_2") (pintype "passive"))
    )
    (net (code "78") (name "Net-(STEPPERDRIVER2-PadMS2)") (class "Default")
      (node (ref "STEPPERDRIVER2") (pin "MS2") (pinfunction "MS2_MS2") (pintype "input"))
      (node (ref "Z-AXIS") (pin "4") (pinfunction "4_4") (pintype "passive"))
    )
    (net (code "79") (name "Net-(STEPPERDRIVER2-PadMS3)") (class "Default")
      (node (ref "STEPPERDRIVER2") (pin "MS3") (pinfunction "MS3_MS3") (pintype "input"))
      (node (ref "Z-AXIS") (pin "6") (pinfunction "6_6") (pintype "passive"))
    )
    (net (code "80") (name "Net-(STEPPERDRIVER2-~{RESET})") (class "Default")
      (node (ref "STEPPERDRIVER2") (pin "!RST") (pinfunction "~{RESET}_!RST") (pintype "input"))
      (node (ref "STEPPERDRIVER2") (pin "!SLP") (pinfunction "~{SLEEP}_!SLP") (pintype "input"))
    )
    (net (code "81") (name "Net-(STEPPERDRIVER3-~{RESET})") (class "Default")
      (node (ref "STEPPERDRIVER3") (pin "!RST") (pinfunction "~{RESET}_!RST") (pintype "input"))
      (node (ref "STEPPERDRIVER3") (pin "!SLP") (pinfunction "~{SLEEP}_!SLP") (pintype "input"))
    )
    (net (code "82") (name "unconnected-(TTL-Pad6)") (class "Default")
      (node (ref "TTL") (pin "6") (pinfunction "6_6") (pintype "passive"))
    )
  )
)
